# fetdrivers.net
KiCad netlist of a schematic drawn in Altium Designer
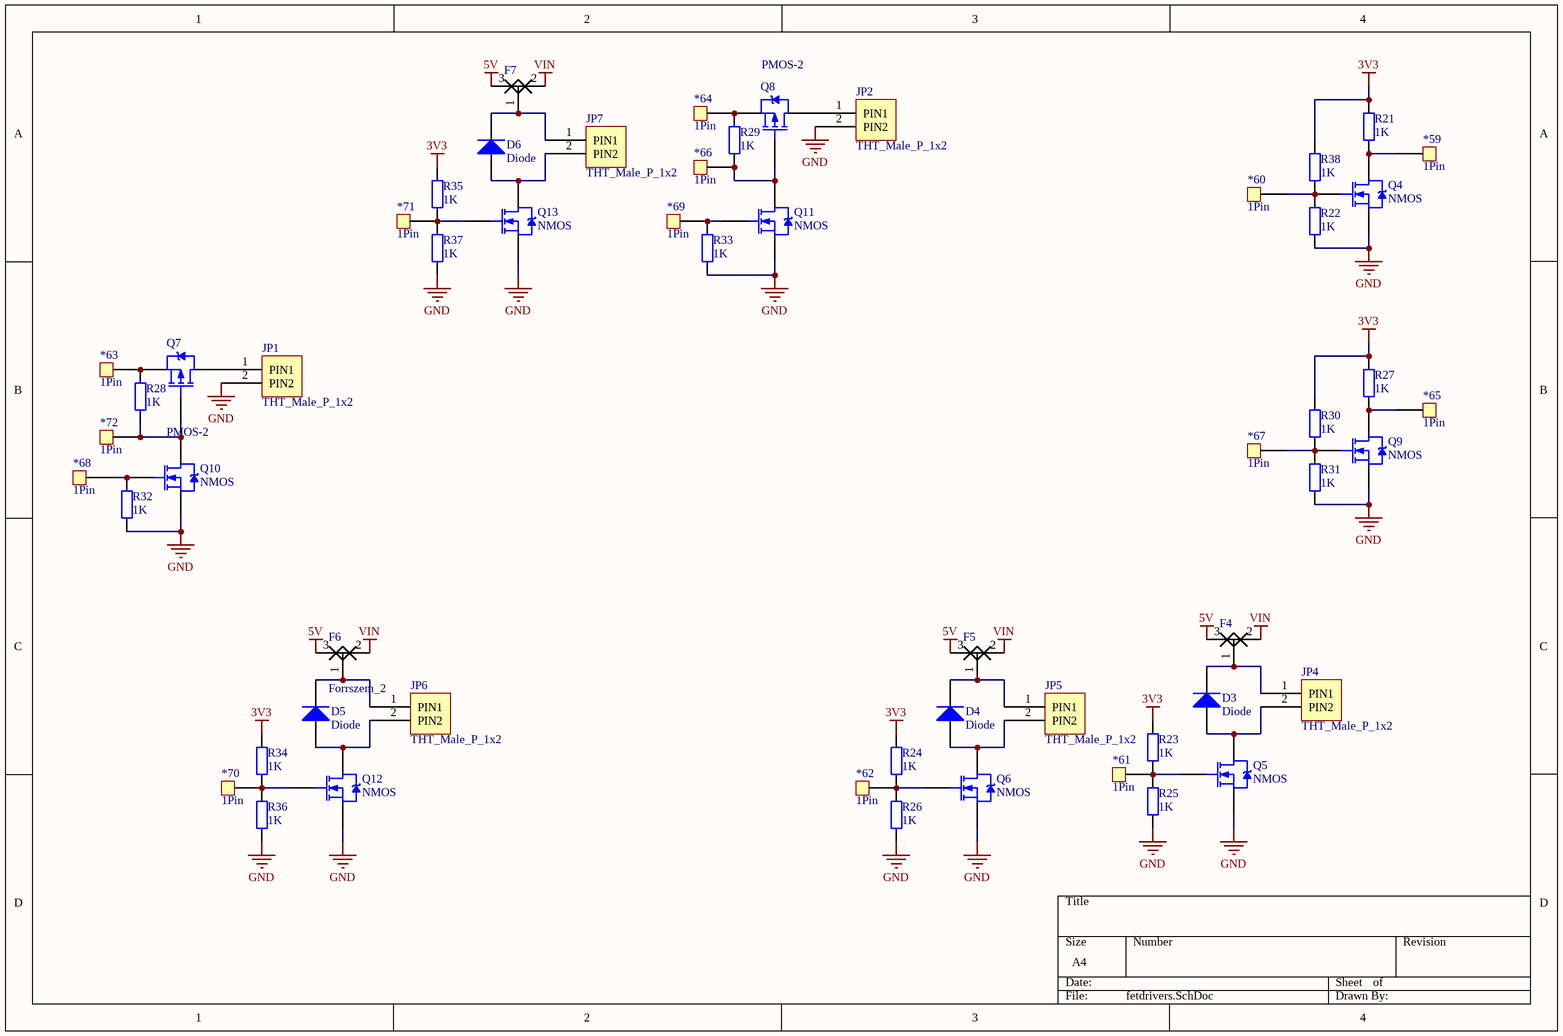
[diagram p0: fetdrivers.SchDoc]

(export (version "E")
  (design (tool "Eeschema 10.0.6"))
  (components
    (comp (ref "*59") (value "1Pin") (footprint "Header1") (libsource (lib "") (part "1Pin_1")))
    (comp (ref "*60") (value "1Pin") (footprint "Header1") (libsource (lib "MySch") (part "1Pin")))
    (comp (ref "*61") (value "1Pin") (footprint "Header1") (libsource (lib "MySch") (part "1Pin")))
    (comp (ref "*62") (value "1Pin") (footprint "Header1") (libsource (lib "MySch") (part "1Pin")))
    (comp (ref "*63") (value "1Pin") (footprint "Header1") (libsource (lib "MySch") (part "1Pin")))
    (comp (ref "*64") (value "1Pin") (footprint "Header1") (libsource (lib "MySch") (part "1Pin")))
    (comp (ref "*65") (value "1Pin") (footprint "Header1") (libsource (lib "") (part "1Pin_1")))
    (comp (ref "*66") (value "1Pin") (footprint "Header1") (libsource (lib "MySch") (part "1Pin")))
    (comp (ref "*67") (value "1Pin") (footprint "Header1") (libsource (lib "MySch") (part "1Pin")))
    (comp (ref "*68") (value "1Pin") (footprint "Header1") (libsource (lib "MySch") (part "1Pin")))
    (comp (ref "*69") (value "1Pin") (footprint "Header1") (libsource (lib "MySch") (part "1Pin")))
    (comp (ref "*70") (value "1Pin") (footprint "Header1") (libsource (lib "MySch") (part "1Pin")))
    (comp (ref "*71") (value "1Pin") (footprint "Header1") (libsource (lib "MySch") (part "1Pin")))
    (comp (ref "*72") (value "1Pin") (footprint "Header1") (libsource (lib "MySch") (part "1Pin")))
    (comp (ref "D3")
      (value "Diode")
      (footprint "DO214")
      (fields (field (name "PUBLISHER") "Altium Limited"))
      (libsource (lib "MySch") (part "Diode"))
    )
    (comp (ref "D4")
      (value "Diode")
      (footprint "DO214")
      (fields (field (name "PUBLISHER") "Altium Limited"))
      (libsource (lib "MySch") (part "Diode"))
    )
    (comp (ref "D5")
      (value "Diode")
      (footprint "DO214")
      (fields (field (name "PUBLISHER") "Altium Limited"))
      (libsource (lib "MySch") (part "Diode"))
    )
    (comp (ref "D6")
      (value "Diode")
      (footprint "DO214")
      (fields (field (name "PUBLISHER") "Altium Limited"))
      (libsource (lib "MySch") (part "Diode"))
    )
    (comp (ref "F4")
      (value "Forrszem_2")
      (footprint "FORRSZEM3")
      (libsource (lib "MySch") (part "Forrszem_2"))
    )
    (comp (ref "F5")
      (value "Forrszem_2")
      (footprint "FORRSZEM3")
      (libsource (lib "MySch") (part "Forrszem_2"))
    )
    (comp (ref "F6")
      (value "Forrszem_2")
      (footprint "FORRSZEM3")
      (libsource (lib "MySch") (part "Forrszem_2"))
    )
    (comp (ref "F7")
      (value "Forrszem_2")
      (footprint "FORRSZEM3")
      (libsource (lib "MySch") (part "Forrszem_2"))
    )
    (comp (ref "JP1")
      (value "THT_Male_P_1x2")
      (footprint "THT_Male_P_1x2-2.54mm")
      (description "THT Male pin header strip 1x2")
      (libsource (lib "Vowstar_Connector") (part "THT_Male_P_1x2"))
    )
    (comp (ref "JP2")
      (value "THT_Male_P_1x2")
      (footprint "THT_Male_P_1x2-2.54mm")
      (description "THT Male pin header strip 1x2")
      (libsource (lib "Vowstar_Connector") (part "THT_Male_P_1x2"))
    )
    (comp (ref "JP4")
      (value "THT_Male_P_1x2")
      (footprint "THT_Male_P_1x2-2.54mm")
      (description "THT Male pin header strip 1x2")
      (libsource (lib "Vowstar_Connector") (part "THT_Male_P_1x2"))
    )
    (comp (ref "JP5")
      (value "THT_Male_P_1x2")
      (footprint "THT_Male_P_1x2-2.54mm")
      (description "THT Male pin header strip 1x2")
      (libsource (lib "Vowstar_Connector") (part "THT_Male_P_1x2"))
    )
    (comp (ref "JP6")
      (value "THT_Male_P_1x2")
      (footprint "THT_Male_P_1x2-2.54mm")
      (description "THT Male pin header strip 1x2")
      (libsource (lib "Vowstar_Connector") (part "THT_Male_P_1x2"))
    )
    (comp (ref "JP7")
      (value "THT_Male_P_1x2")
      (footprint "THT_Male_P_1x2-2.54mm")
      (description "THT Male pin header strip 1x2")
      (libsource (lib "Vowstar_Connector") (part "THT_Male_P_1x2"))
    )
    (comp (ref "Q4")
      (value "NMOS")
      (footprint "SOT95P245X110-3N")
      (description "N-Channel Power MOSFET")
      (fields (field (name "PUBLISHER") "Altium Limited"))
      (libsource (lib "MySch") (part "NMOS"))
    )
    (comp (ref "Q5")
      (value "NMOS")
      (footprint "SOT95P245X110-3N")
      (description "N-Channel Power MOSFET")
      (fields (field (name "PUBLISHER") "Altium Limited"))
      (libsource (lib "MySch") (part "NMOS"))
    )
    (comp (ref "Q6")
      (value "NMOS")
      (footprint "SOT95P245X110-3N")
      (description "N-Channel Power MOSFET")
      (fields (field (name "PUBLISHER") "Altium Limited"))
      (libsource (lib "MySch") (part "NMOS"))
    )
    (comp (ref "Q7")
      (value "PMOS-2")
      (footprint "SOT95P245X110-3N")
      (description "P-Channel Power MOSFET")
      (fields (field (name "PUBLISHER") "Altium Limited"))
      (libsource (lib "MySch") (part "PMOS-2"))
    )
    (comp (ref "Q8")
      (value "PMOS-2")
      (footprint "SOT95P245X110-3N")
      (description "P-Channel Power MOSFET")
      (fields (field (name "PUBLISHER") "Altium Limited"))
      (libsource (lib "MySch") (part "PMOS-2"))
    )
    (comp (ref "Q9")
      (value "NMOS")
      (footprint "SOT95P245X110-3N")
      (description "N-Channel Power MOSFET")
      (fields (field (name "PUBLISHER") "Altium Limited"))
      (libsource (lib "MySch") (part "NMOS"))
    )
    (comp (ref "Q10")
      (value "NMOS")
      (footprint "SOT95P245X110-3N")
      (description "N-Channel Power MOSFET")
      (fields (field (name "PUBLISHER") "Altium Limited"))
      (libsource (lib "MySch") (part "NMOS"))
    )
    (comp (ref "Q11")
      (value "NMOS")
      (footprint "SOT95P245X110-3N")
      (description "N-Channel Power MOSFET")
      (fields (field (name "PUBLISHER") "Altium Limited"))
      (libsource (lib "MySch") (part "NMOS"))
    )
    (comp (ref "Q12")
      (value "NMOS")
      (footprint "SOT95P245X110-3N")
      (description "N-Channel Power MOSFET")
      (fields (field (name "PUBLISHER") "Altium Limited"))
      (libsource (lib "MySch") (part "NMOS"))
    )
    (comp (ref "Q13")
      (value "NMOS")
      (footprint "SOT95P245X110-3N")
      (description "N-Channel Power MOSFET")
      (fields (field (name "PUBLISHER") "Altium Limited"))
      (libsource (lib "MySch") (part "NMOS"))
    )
    (comp (ref "R21")
      (value "1K")
      (footprint "0805")
      (description "Resistor")
      (fields (field (name "PUBLISHER") "Altium Limited"))
      (libsource (lib "MySch") (part "Resistor"))
    )
    (comp (ref "R22")
      (value "1K")
      (footprint "0805")
      (description "Resistor")
      (fields (field (name "PUBLISHER") "Altium Limited"))
      (libsource (lib "MySch") (part "Resistor"))
    )
    (comp (ref "R23")
      (value "1K")
      (footprint "0805")
      (description "Resistor")
      (fields (field (name "PUBLISHER") "Altium Limited"))
      (libsource (lib "MySch") (part "Resistor"))
    )
    (comp (ref "R24")
      (value "1K")
      (footprint "0805")
      (description "Resistor")
      (fields (field (name "PUBLISHER") "Altium Limited"))
      (libsource (lib "MySch") (part "Resistor"))
    )
    (comp (ref "R25")
      (value "1K")
      (footprint "0805")
      (description "Resistor")
      (fields (field (name "PUBLISHER") "Altium Limited"))
      (libsource (lib "MySch") (part "Resistor"))
    )
    (comp (ref "R26")
      (value "1K")
      (footprint "0805")
      (description "Resistor")
      (fields (field (name "PUBLISHER") "Altium Limited"))
      (libsource (lib "MySch") (part "Resistor"))
    )
    (comp (ref "R27")
      (value "1K")
      (footprint "0805")
      (description "Resistor")
      (fields (field (name "PUBLISHER") "Altium Limited"))
      (libsource (lib "MySch") (part "Resistor"))
    )
    (comp (ref "R28")
      (value "1K")
      (footprint "FP_0805_RES")
      (description "Resistor")
      (libsource (lib "MySch") (part "RES"))
    )
    (comp (ref "R29")
      (value "1K")
      (footprint "FP_0805_RES")
      (description "Resistor")
      (libsource (lib "MySch") (part "RES"))
    )
    (comp (ref "R30")
      (value "1K")
      (footprint "0805")
      (description "Resistor")
      (fields (field (name "PUBLISHER") "Altium Limited"))
      (libsource (lib "MySch") (part "Resistor"))
    )
    (comp (ref "R31")
      (value "1K")
      (footprint "0805")
      (description "Resistor")
      (fields (field (name "PUBLISHER") "Altium Limited"))
      (libsource (lib "MySch") (part "Resistor"))
    )
    (comp (ref "R32")
      (value "1K")
      (footprint "FP_0805_RES")
      (description "Resistor")
      (libsource (lib "MySch") (part "RES"))
    )
    (comp (ref "R33")
      (value "1K")
      (footprint "FP_0805_RES")
      (description "Resistor")
      (libsource (lib "MySch") (part "RES"))
    )
    (comp (ref "R34")
      (value "1K")
      (footprint "0805")
      (description "Resistor")
      (fields (field (name "PUBLISHER") "Altium Limited"))
      (libsource (lib "MySch") (part "Resistor"))
    )
    (comp (ref "R35")
      (value "1K")
      (footprint "0805")
      (description "Resistor")
      (fields (field (name "PUBLISHER") "Altium Limited"))
      (libsource (lib "MySch") (part "Resistor"))
    )
    (comp (ref "R36")
      (value "1K")
      (footprint "0805")
      (description "Resistor")
      (fields (field (name "PUBLISHER") "Altium Limited"))
      (libsource (lib "MySch") (part "Resistor"))
    )
    (comp (ref "R37")
      (value "1K")
      (footprint "0805")
      (description "Resistor")
      (fields (field (name "PUBLISHER") "Altium Limited"))
      (libsource (lib "MySch") (part "Resistor"))
    )
    (comp (ref "R38")
      (value "1K")
      (footprint "0805")
      (description "Resistor")
      (fields (field (name "PUBLISHER") "Altium Limited"))
      (libsource (lib "MySch") (part "Resistor"))
    )
  )
  (nets
    (net (code "1") (name "3V3") (class "Default")
      (node (ref "R21") (pin "2") (pinfunction "2_2") (pintype "passive"))
      (node (ref "R23") (pin "2") (pinfunction "2_2") (pintype "passive"))
      (node (ref "R24") (pin "2") (pinfunction "2_2") (pintype "passive"))
      (node (ref "R27") (pin "2") (pinfunction "2_2") (pintype "passive"))
      (node (ref "R30") (pin "2") (pinfunction "2_2") (pintype "passive"))
      (node (ref "R34") (pin "2") (pinfunction "2_2") (pintype "passive"))
      (node (ref "R35") (pin "2") (pinfunction "2_2") (pintype "passive"))
      (node (ref "R38") (pin "2") (pinfunction "2_2") (pintype "passive"))
    )
    (net (code "2") (name "5V") (class "Default")
      (node (ref "F4") (pin "3") (pinfunction "A_3") (pintype "passive"))
      (node (ref "F5") (pin "3") (pinfunction "A_3") (pintype "passive"))
      (node (ref "F6") (pin "3") (pinfunction "A_3") (pintype "passive"))
      (node (ref "F7") (pin "3") (pinfunction "A_3") (pintype "passive"))
    )
    (net (code "3") (name "GND") (class "Default")
      (node (ref "JP1") (pin "2") (pinfunction "PIN2_2") (pintype "passive"))
      (node (ref "JP2") (pin "2") (pinfunction "PIN2_2") (pintype "passive"))
      (node (ref "Q10") (pin "S") (pinfunction "S_S") (pintype "passive"))
      (node (ref "Q11") (pin "S") (pinfunction "S_S") (pintype "passive"))
      (node (ref "Q12") (pin "S") (pinfunction "S_S") (pintype "passive"))
      (node (ref "Q13") (pin "S") (pinfunction "S_S") (pintype "passive"))
      (node (ref "Q4") (pin "S") (pinfunction "S_S") (pintype "passive"))
      (node (ref "Q5") (pin "S") (pinfunction "S_S") (pintype "passive"))
      (node (ref "Q6") (pin "S") (pinfunction "S_S") (pintype "passive"))
      (node (ref "Q9") (pin "S") (pinfunction "S_S") (pintype "passive"))
      (node (ref "R22") (pin "1") (pinfunction "1_1") (pintype "passive"))
      (node (ref "R25") (pin "1") (pinfunction "1_1") (pintype "passive"))
      (node (ref "R26") (pin "1") (pinfunction "1_1") (pintype "passive"))
      (node (ref "R31") (pin "1") (pinfunction "1_1") (pintype "passive"))
      (node (ref "R32") (pin "1") (pinfunction "1_1") (pintype "passive"))
      (node (ref "R33") (pin "1") (pinfunction "1_1") (pintype "passive"))
      (node (ref "R36") (pin "1") (pinfunction "1_1") (pintype "passive"))
      (node (ref "R37") (pin "1") (pinfunction "1_1") (pintype "passive"))
    )
    (net (code "4") (name "Net-(*59-Pad1)") (class "Default")
      (node (ref "*59") (pin "1") (pinfunction "1_1") (pintype "passive"))
      (node (ref "Q4") (pin "D") (pinfunction "D_D") (pintype "passive"))
      (node (ref "R21") (pin "1") (pinfunction "1_1") (pintype "passive"))
    )
    (net (code "5") (name "Net-(*60-Pad1)") (class "Default")
      (node (ref "*60") (pin "1") (pinfunction "1_1") (pintype "passive"))
      (node (ref "Q4") (pin "G") (pinfunction "G_G") (pintype "passive"))
      (node (ref "R22") (pin "2") (pinfunction "2_2") (pintype "passive"))
      (node (ref "R38") (pin "1") (pinfunction "1_1") (pintype "passive"))
    )
    (net (code "6") (name "Net-(*61-Pad1)") (class "Default")
      (node (ref "*61") (pin "1") (pinfunction "1_1") (pintype "passive"))
      (node (ref "Q5") (pin "G") (pinfunction "G_G") (pintype "passive"))
      (node (ref "R23") (pin "1") (pinfunction "1_1") (pintype "passive"))
      (node (ref "R25") (pin "2") (pinfunction "2_2") (pintype "passive"))
    )
    (net (code "7") (name "Net-(*62-Pad1)") (class "Default")
      (node (ref "*62") (pin "1") (pinfunction "1_1") (pintype "passive"))
      (node (ref "Q6") (pin "G") (pinfunction "G_G") (pintype "passive"))
      (node (ref "R24") (pin "1") (pinfunction "1_1") (pintype "passive"))
      (node (ref "R26") (pin "2") (pinfunction "2_2") (pintype "passive"))
    )
    (net (code "8") (name "Net-(*63-Pad1)") (class "Default")
      (node (ref "*63") (pin "1") (pinfunction "1_1") (pintype "passive"))
      (node (ref "Q7") (pin "S") (pinfunction "S_S") (pintype "passive"))
      (node (ref "R28") (pin "2") (pinfunction "2_2") (pintype "passive"))
    )
    (net (code "9") (name "Net-(*64-Pad1)") (class "Default")
      (node (ref "*64") (pin "1") (pinfunction "1_1") (pintype "passive"))
      (node (ref "Q8") (pin "S") (pinfunction "S_S") (pintype "passive"))
      (node (ref "R29") (pin "2") (pinfunction "2_2") (pintype "passive"))
    )
    (net (code "10") (name "Net-(*65-Pad1)") (class "Default")
      (node (ref "*65") (pin "1") (pinfunction "1_1") (pintype "passive"))
      (node (ref "Q9") (pin "D") (pinfunction "D_D") (pintype "passive"))
      (node (ref "R27") (pin "1") (pinfunction "1_1") (pintype "passive"))
    )
    (net (code "11") (name "Net-(*66-Pad1)") (class "Default")
      (node (ref "*66") (pin "1") (pinfunction "1_1") (pintype "passive"))
      (node (ref "Q11") (pin "D") (pinfunction "D_D") (pintype "passive"))
      (node (ref "Q8") (pin "G") (pinfunction "G_G") (pintype "passive"))
      (node (ref "R29") (pin "1") (pinfunction "1_1") (pintype "passive"))
    )
    (net (code "12") (name "Net-(*67-Pad1)") (class "Default")
      (node (ref "*67") (pin "1") (pinfunction "1_1") (pintype "passive"))
      (node (ref "Q9") (pin "G") (pinfunction "G_G") (pintype "passive"))
      (node (ref "R30") (pin "1") (pinfunction "1_1") (pintype "passive"))
      (node (ref "R31") (pin "2") (pinfunction "2_2") (pintype "passive"))
    )
    (net (code "13") (name "Net-(*68-Pad1)") (class "Default")
      (node (ref "*68") (pin "1") (pinfunction "1_1") (pintype "passive"))
      (node (ref "Q10") (pin "G") (pinfunction "G_G") (pintype "passive"))
      (node (ref "R32") (pin "2") (pinfunction "2_2") (pintype "passive"))
    )
    (net (code "14") (name "Net-(*69-Pad1)") (class "Default")
      (node (ref "*69") (pin "1") (pinfunction "1_1") (pintype "passive"))
      (node (ref "Q11") (pin "G") (pinfunction "G_G") (pintype "passive"))
      (node (ref "R33") (pin "2") (pinfunction "2_2") (pintype "passive"))
    )
    (net (code "15") (name "Net-(*70-Pad1)") (class "Default")
      (node (ref "*70") (pin "1") (pinfunction "1_1") (pintype "passive"))
      (node (ref "Q12") (pin "G") (pinfunction "G_G") (pintype "passive"))
      (node (ref "R34") (pin "1") (pinfunction "1_1") (pintype "passive"))
      (node (ref "R36") (pin "2") (pinfunction "2_2") (pintype "passive"))
    )
    (net (code "16") (name "Net-(*71-Pad1)") (class "Default")
      (node (ref "*71") (pin "1") (pinfunction "1_1") (pintype "passive"))
      (node (ref "Q13") (pin "G") (pinfunction "G_G") (pintype "passive"))
      (node (ref "R35") (pin "1") (pinfunction "1_1") (pintype "passive"))
      (node (ref "R37") (pin "2") (pinfunction "2_2") (pintype "passive"))
    )
    (net (code "17") (name "Net-(*72-Pad1)") (class "Default")
      (node (ref "*72") (pin "1") (pinfunction "1_1") (pintype "passive"))
      (node (ref "Q10") (pin "D") (pinfunction "D_D") (pintype "passive"))
      (node (ref "Q7") (pin "G") (pinfunction "G_G") (pintype "passive"))
      (node (ref "R28") (pin "1") (pinfunction "1_1") (pintype "passive"))
    )
    (net (code "18") (name "Net-(D3-A)") (class "Default")
      (node (ref "D3") (pin "1") (pinfunction "A_1") (pintype "passive"))
      (node (ref "JP4") (pin "2") (pinfunction "PIN2_2") (pintype "passive"))
      (node (ref "Q5") (pin "D") (pinfunction "D_D") (pintype "passive"))
    )
    (net (code "19") (name "Net-(D3-K)") (class "Default")
      (node (ref "D3") (pin "2") (pinfunction "K_2") (pintype "passive"))
      (node (ref "F4") (pin "1") (pinfunction "B_1") (pintype "passive"))
      (node (ref "JP4") (pin "1") (pinfunction "PIN1_1") (pintype "passive"))
    )
    (net (code "20") (name "Net-(D4-A)") (class "Default")
      (node (ref "D4") (pin "1") (pinfunction "A_1") (pintype "passive"))
      (node (ref "JP5") (pin "2") (pinfunction "PIN2_2") (pintype "passive"))
      (node (ref "Q6") (pin "D") (pinfunction "D_D") (pintype "passive"))
    )
    (net (code "21") (name "Net-(D4-K)") (class "Default")
      (node (ref "D4") (pin "2") (pinfunction "K_2") (pintype "passive"))
      (node (ref "F5") (pin "1") (pinfunction "B_1") (pintype "passive"))
      (node (ref "JP5") (pin "1") (pinfunction "PIN1_1") (pintype "passive"))
    )
    (net (code "22") (name "Net-(D5-A)") (class "Default")
      (node (ref "D5") (pin "1") (pinfunction "A_1") (pintype "passive"))
      (node (ref "JP6") (pin "2") (pinfunction "PIN2_2") (pintype "passive"))
      (node (ref "Q12") (pin "D") (pinfunction "D_D") (pintype "passive"))
    )
    (net (code "23") (name "Net-(D5-K)") (class "Default")
      (node (ref "D5") (pin "2") (pinfunction "K_2") (pintype "passive"))
      (node (ref "F6") (pin "1") (pinfunction "B_1") (pintype "passive"))
      (node (ref "JP6") (pin "1") (pinfunction "PIN1_1") (pintype "passive"))
    )
    (net (code "24") (name "Net-(D6-A)") (class "Default")
      (node (ref "D6") (pin "1") (pinfunction "A_1") (pintype "passive"))
      (node (ref "JP7") (pin "2") (pinfunction "PIN2_2") (pintype "passive"))
      (node (ref "Q13") (pin "D") (pinfunction "D_D") (pintype "passive"))
    )
    (net (code "25") (name "Net-(D6-K)") (class "Default")
      (node (ref "D6") (pin "2") (pinfunction "K_2") (pintype "passive"))
      (node (ref "F7") (pin "1") (pinfunction "B_1") (pintype "passive"))
      (node (ref "JP7") (pin "1") (pinfunction "PIN1_1") (pintype "passive"))
    )
    (net (code "26") (name "Net-(JP1-PIN1)") (class "Default")
      (node (ref "JP1") (pin "1") (pinfunction "PIN1_1") (pintype "passive"))
      (node (ref "Q7") (pin "D") (pinfunction "D_D") (pintype "passive"))
    )
    (net (code "27") (name "Net-(JP2-PIN1)") (class "Default")
      (node (ref "JP2") (pin "1") (pinfunction "PIN1_1") (pintype "passive"))
      (node (ref "Q8") (pin "D") (pinfunction "D_D") (pintype "passive"))
    )
    (net (code "28") (name "VIN") (class "Default")
      (node (ref "F4") (pin "2") (pinfunction "C_2") (pintype "passive"))
      (node (ref "F5") (pin "2") (pinfunction "C_2") (pintype "passive"))
      (node (ref "F6") (pin "2") (pinfunction "C_2") (pintype "passive"))
      (node (ref "F7") (pin "2") (pinfunction "C_2") (pintype "passive"))
    )
  )
)
